# Sheet3-can.net
KiCad netlist of a schematic drawn in Altium Designer
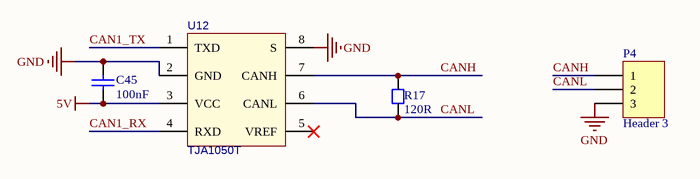
[diagram p0: Sheet3-can.SchDoc]

(export (version "E")
  (design (tool "Eeschema 10.0.6"))
  (components
    (comp (ref "C45")
      (value "100nF")
      (footprint "CC1608-0603")
      (description "0603封装的电容")
      (fields (field (name "PUBLISHER") "Altium Limited"))
      (libsource (lib "base") (part "Cap Chip 0603"))
    )
    (comp (ref "P4")
      (value "Header 3")
      (footprint "HX2.54-3")
      (description "Header, 3-Pin")
      (fields (field (name "PUBLISHER") "Altium Limited"))
      (libsource (lib "Connectors") (part "Header 3"))
    )
    (comp (ref "R17")
      (value "120R")
      (footprint "CR1608-0603")
      (description "0603封装电阻")
      (fields (field (name "PUBLISHER") "Altium Limited"))
      (libsource (lib "base") (part "Resistor Chip 0603"))
    )
    (comp (ref "U12")
      (value "TJA1050T")
      (footprint "SOIC-8")
      (description "1Mhz Can芯片，兼容3.3~5V设备")
      (fields
        (field (name "BOM_MANUFACTURER PART") "TJA1050T/CM,118")
        (field (name "BOM_SUPPLIER PART") "C6952")
      )
      (libsource (lib "PB-Chip") (part "TJA1050T"))
    )
  )
  (nets
    (net (code "1") (name "/CAN1_RX") (class "Default")
      (node (ref "U12") (pin "4") (pinfunction "RXD_4") (pintype "passive"))
    )
    (net (code "2") (name "/CAN1_TX") (class "Default")
      (node (ref "U12") (pin "1") (pinfunction "TXD_1") (pintype "passive"))
    )
    (net (code "3") (name "/CANH") (class "Default")
      (node (ref "P4") (pin "1") (pinfunction "1_1") (pintype "passive"))
      (node (ref "R17") (pin "2") (pinfunction "2_2") (pintype "passive"))
      (node (ref "U12") (pin "7") (pinfunction "CANH_7") (pintype "passive"))
    )
    (net (code "4") (name "/CANL") (class "Default")
      (node (ref "P4") (pin "2") (pinfunction "2_2") (pintype "passive"))
      (node (ref "R17") (pin "1") (pinfunction "1_1") (pintype "passive"))
      (node (ref "U12") (pin "6") (pinfunction "CANL_6") (pintype "passive"))
    )
    (net (code "5") (name "5V") (class "Default")
      (node (ref "C45") (pin "1") (pinfunction "1_1") (pintype "passive"))
      (node (ref "U12") (pin "3") (pinfunction "VCC_3") (pintype "passive"))
    )
    (net (code "6") (name "GND") (class "Default")
      (node (ref "C45") (pin "2") (pinfunction "2_2") (pintype "passive"))
      (node (ref "P4") (pin "3") (pinfunction "3_3") (pintype "passive"))
      (node (ref "U12") (pin "2") (pinfunction "GND_2") (pintype "passive"))
      (node (ref "U12") (pin "8") (pinfunction "S_8") (pintype "passive"))
    )
    (net (code "7") (name "unconnected-(U12-VREF-Pad5)") (class "Default")
      (node (ref "U12") (pin "5") (pinfunction "VREF_5") (pintype "passive+no_connect"))
    )
  )
)
